# T06_preliminarySchematic_v3.net
KiCad netlist of a schematic drawn in EAGLE
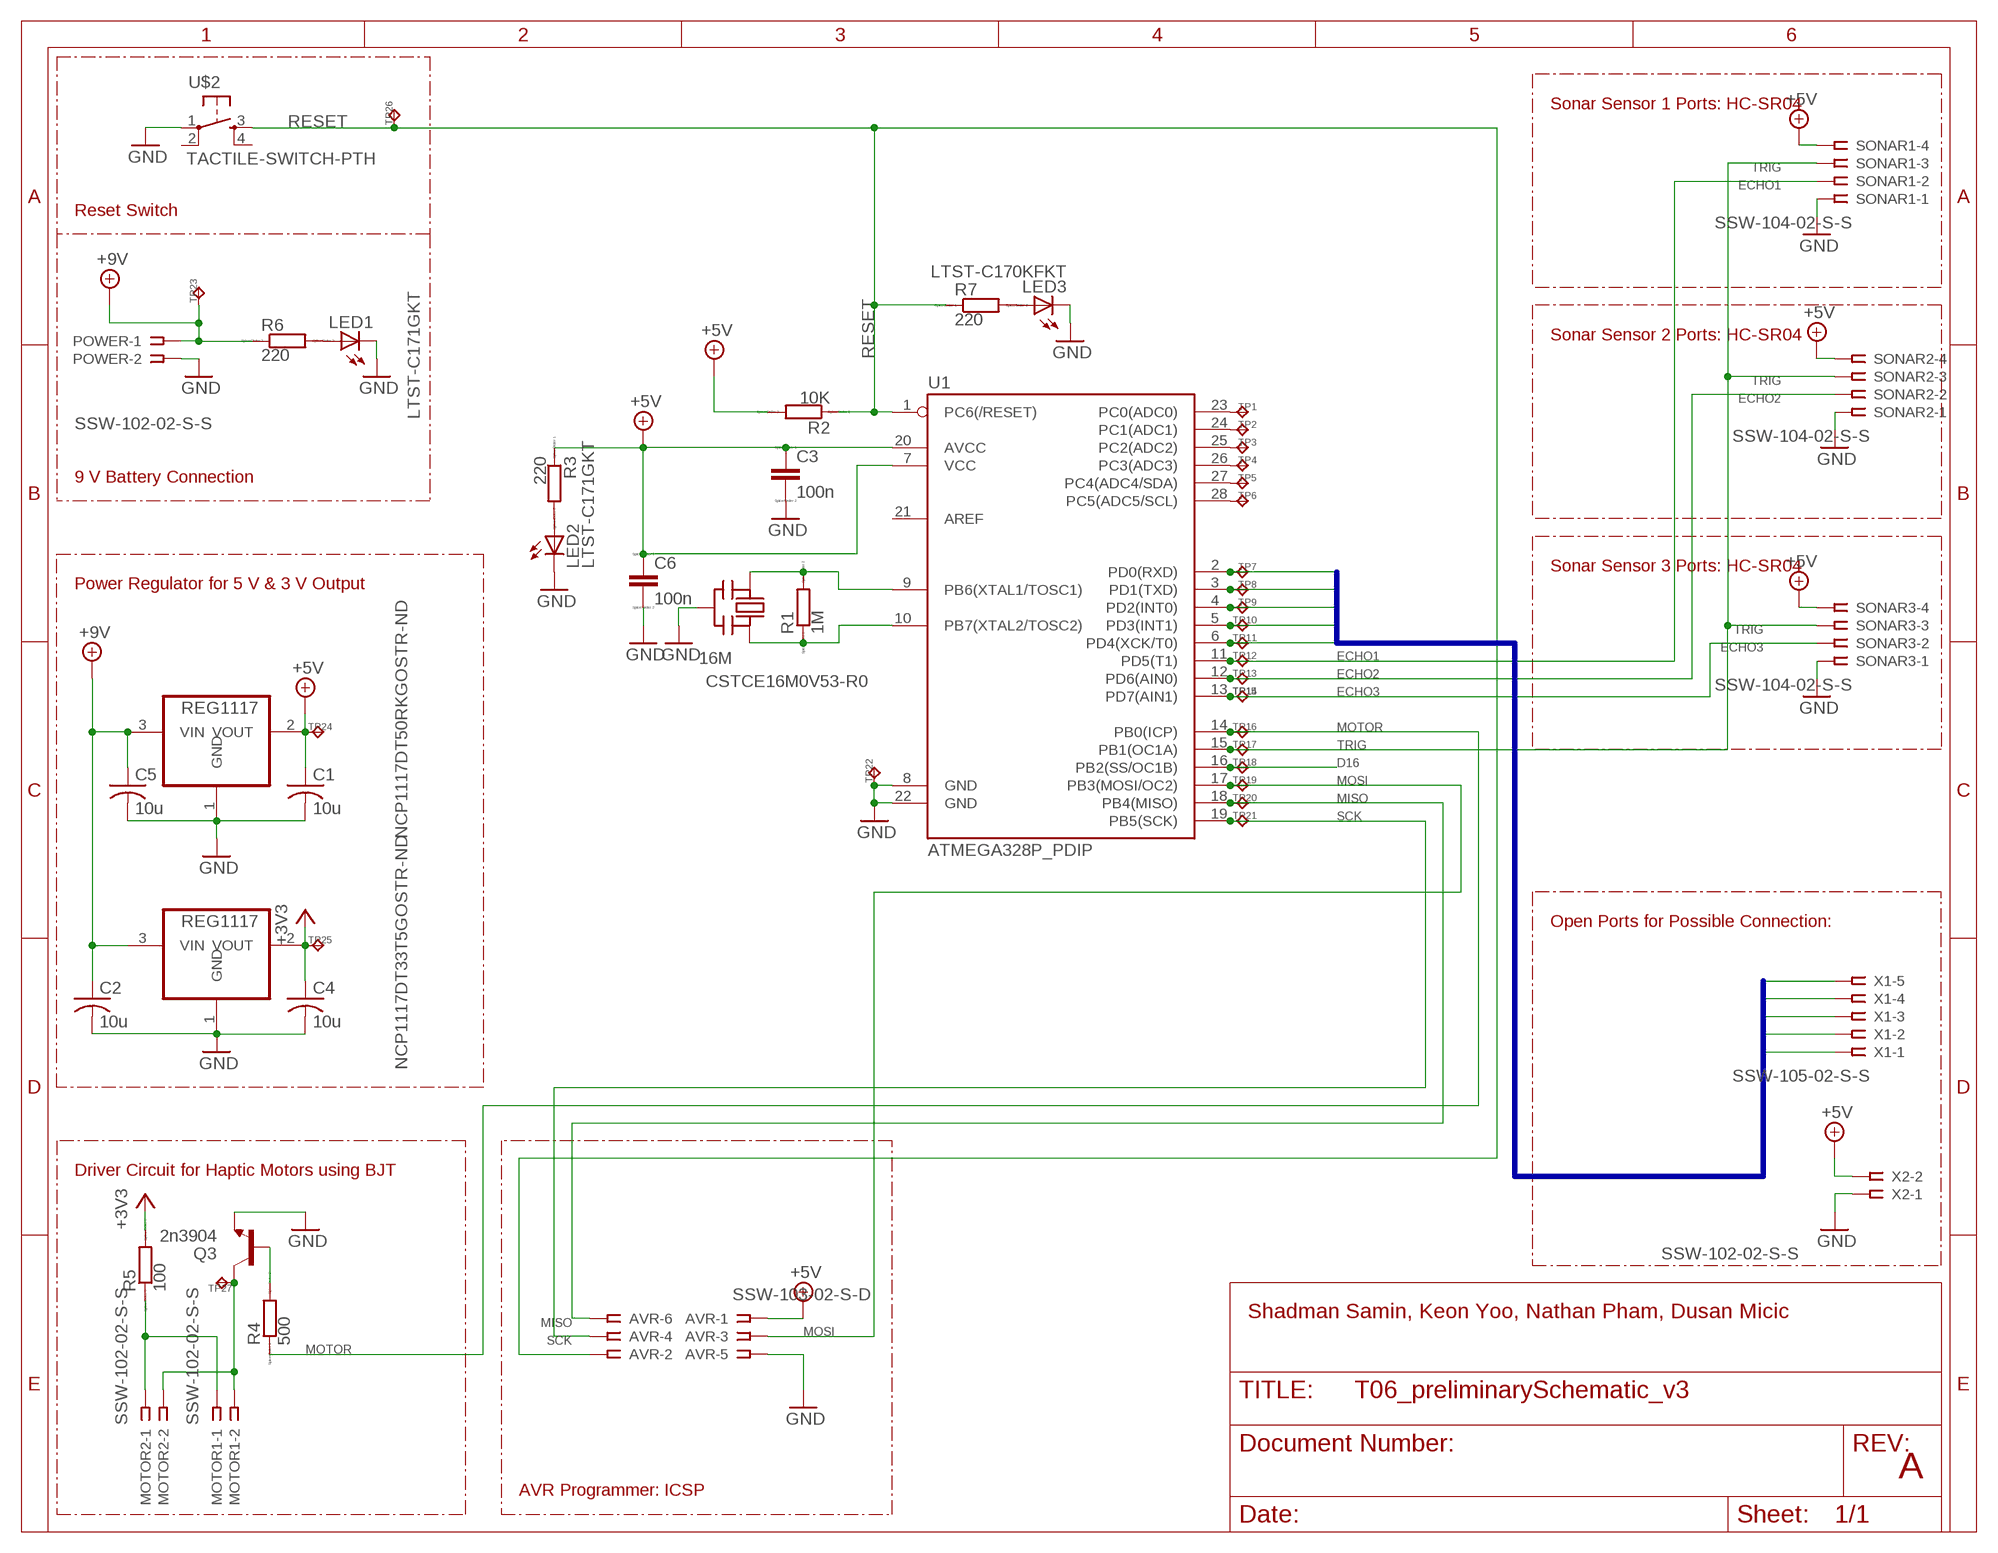
[diagram p0: schematic, sheet 1]

(export (version "E")
  (design (tool "Eeschema 10.0.6"))
  (components
    (comp (ref "AVR")
      (value "SSW-103-02-S-D")
      (footprint "eagle-import:SSW-103-02-S-D")
      (libsource (lib "eagle-import") (part "SSW-103-02-S-D"))
    )
    (comp (ref "C1")
      (value "10u")
      (footprint "eagle-import:C0805K")
      (libsource (lib "eagle-import") (part "C-USC0805K"))
    )
    (comp (ref "C2")
      (value "10u")
      (footprint "eagle-import:C0805K")
      (libsource (lib "eagle-import") (part "C-USC0805K"))
    )
    (comp (ref "C3")
      (value "100n")
      (footprint "eagle-import:C1005")
      (libsource (lib "eagle-import") (part "CC1005"))
    )
    (comp (ref "C4")
      (value "10u")
      (footprint "eagle-import:C0805K")
      (libsource (lib "eagle-import") (part "C-USC0805K"))
    )
    (comp (ref "C5")
      (value "10u")
      (footprint "eagle-import:C0805K")
      (libsource (lib "eagle-import") (part "C-USC0805K"))
    )
    (comp (ref "C6")
      (value "100n")
      (footprint "eagle-import:C1005")
      (libsource (lib "eagle-import") (part "CC1005"))
    )
    (comp (ref "CSTCE16M0V53-R0")
      (value "16M")
      (footprint "eagle-import:CSTCR-G")
      (libsource (lib "eagle-import") (part "CERMOSCILL-CSTCRG"))
    )
    (comp (ref "LED1")
      (value "LTST-C171GKT")
      (footprint "eagle-import:CHIPLED_0805")
      (libsource (lib "eagle-import") (part "LEDCHIPLED_0805"))
    )
    (comp (ref "LED2")
      (value "LTST-C171GKT")
      (footprint "eagle-import:CHIP-LED0805")
      (libsource (lib "eagle-import") (part "LEDCHIP-LED0805"))
    )
    (comp (ref "LED3")
      (value "LTST-C170KFKT")
      (footprint "eagle-import:CHIP-LED0805")
      (libsource (lib "eagle-import") (part "LEDCHIP-LED0805"))
    )
    (comp (ref "MOTOR1")
      (value "SSW-102-02-S-S")
      (footprint "eagle-import:SSW-102-02-S-S")
      (libsource (lib "eagle-import") (part "SSW-102-02-S-S"))
    )
    (comp (ref "MOTOR2")
      (value "SSW-102-02-S-S")
      (footprint "eagle-import:SSW-102-02-S-S")
      (libsource (lib "eagle-import") (part "SSW-102-02-S-S"))
    )
    (comp (ref "NCP1117DT33T5GOSTR-ND")
      (value "REG1117")
      (footprint "eagle-import:SOT223")
      (libsource (lib "eagle-import") (part "REG1117"))
    )
    (comp (ref "NCP1117DT50RKGOSTR-ND")
      (value "REG1117")
      (footprint "eagle-import:SOT223")
      (libsource (lib "eagle-import") (part "REG1117"))
    )
    (comp (ref "POWER")
      (value "SSW-102-02-S-S")
      (footprint "eagle-import:SSW-102-02-S-S")
      (libsource (lib "eagle-import") (part "SSW-102-02-S-S"))
    )
    (comp (ref "Q3")
      (value "2n3904")
      (footprint "eagle-import:TO-92")
      (libsource (lib "eagle-import") (part "TRANSISTOR_NPN2N3904"))
    )
    (comp (ref "R1")
      (value "1M")
      (footprint "eagle-import:R0603")
      (libsource (lib "eagle-import") (part "RR0603"))
    )
    (comp (ref "R2")
      (value "10K")
      (footprint "eagle-import:R0603")
      (libsource (lib "eagle-import") (part "RR0603"))
    )
    (comp (ref "R3")
      (value "220")
      (footprint "eagle-import:R0603")
      (libsource (lib "eagle-import") (part "RR0603"))
    )
    (comp (ref "R4")
      (value "500")
      (footprint "eagle-import:R0603")
      (libsource (lib "eagle-import") (part "RR0603"))
    )
    (comp (ref "R5")
      (value "100")
      (footprint "eagle-import:R0603")
      (libsource (lib "eagle-import") (part "RR0603"))
    )
    (comp (ref "R6")
      (value "220")
      (footprint "eagle-import:R0603")
      (libsource (lib "eagle-import") (part "RR0603"))
    )
    (comp (ref "R7")
      (value "220")
      (footprint "eagle-import:R0603")
      (libsource (lib "eagle-import") (part "RR0603"))
    )
    (comp (ref "SONAR1")
      (value "SSW-104-02-S-S")
      (footprint "eagle-import:SSW-104-02-S-S")
      (libsource (lib "eagle-import") (part "SSW-104-02-S-S"))
    )
    (comp (ref "SONAR2")
      (value "SSW-104-02-S-S")
      (footprint "eagle-import:SSW-104-02-S-S")
      (libsource (lib "eagle-import") (part "SSW-104-02-S-S"))
    )
    (comp (ref "SONAR3")
      (value "SSW-104-02-S-S")
      (footprint "eagle-import:SSW-104-02-S-S")
      (libsource (lib "eagle-import") (part "SSW-104-02-S-S"))
    )
    (comp (ref "TP1")
      (value "TPPAD1-13")
      (footprint "eagle-import:P1-13")
      (libsource (lib "eagle-import") (part "TPPAD1-13"))
    )
    (comp (ref "TP2")
      (value "TPPAD1-13")
      (footprint "eagle-import:P1-13")
      (libsource (lib "eagle-import") (part "TPPAD1-13"))
    )
    (comp (ref "TP3")
      (value "TPPAD1-13")
      (footprint "eagle-import:P1-13")
      (libsource (lib "eagle-import") (part "TPPAD1-13"))
    )
    (comp (ref "TP4")
      (value "TPPAD1-13")
      (footprint "eagle-import:P1-13")
      (libsource (lib "eagle-import") (part "TPPAD1-13"))
    )
    (comp (ref "TP5")
      (value "TPPAD1-13")
      (footprint "eagle-import:P1-13")
      (libsource (lib "eagle-import") (part "TPPAD1-13"))
    )
    (comp (ref "TP6")
      (value "TPPAD1-13")
      (footprint "eagle-import:P1-13")
      (libsource (lib "eagle-import") (part "TPPAD1-13"))
    )
    (comp (ref "TP7")
      (value "TPPAD1-13")
      (footprint "eagle-import:P1-13")
      (libsource (lib "eagle-import") (part "TPPAD1-13"))
    )
    (comp (ref "TP8")
      (value "TPPAD1-13")
      (footprint "eagle-import:P1-13")
      (libsource (lib "eagle-import") (part "TPPAD1-13"))
    )
    (comp (ref "TP9")
      (value "TPPAD1-13")
      (footprint "eagle-import:P1-13")
      (libsource (lib "eagle-import") (part "TPPAD1-13"))
    )
    (comp (ref "TP10")
      (value "TPPAD1-13")
      (footprint "eagle-import:P1-13")
      (libsource (lib "eagle-import") (part "TPPAD1-13"))
    )
    (comp (ref "TP11")
      (value "TPPAD1-13")
      (footprint "eagle-import:P1-13")
      (libsource (lib "eagle-import") (part "TPPAD1-13"))
    )
    (comp (ref "TP12")
      (value "TPPAD1-13")
      (footprint "eagle-import:P1-13")
      (libsource (lib "eagle-import") (part "TPPAD1-13"))
    )
    (comp (ref "TP13")
      (value "TPPAD1-13")
      (footprint "eagle-import:P1-13")
      (libsource (lib "eagle-import") (part "TPPAD1-13"))
    )
    (comp (ref "TP14")
      (value "TPPAD1-13")
      (footprint "eagle-import:P1-13")
      (libsource (lib "eagle-import") (part "TPPAD1-13"))
    )
    (comp (ref "TP15")
      (value "TPPAD1-13")
      (footprint "eagle-import:P1-13")
      (libsource (lib "eagle-import") (part "TPPAD1-13"))
    )
    (comp (ref "TP16")
      (value "TPPAD1-13")
      (footprint "eagle-import:P1-13")
      (libsource (lib "eagle-import") (part "TPPAD1-13"))
    )
    (comp (ref "TP17")
      (value "TPPAD1-13")
      (footprint "eagle-import:P1-13")
      (libsource (lib "eagle-import") (part "TPPAD1-13"))
    )
    (comp (ref "TP18")
      (value "TPPAD1-13")
      (footprint "eagle-import:P1-13")
      (libsource (lib "eagle-import") (part "TPPAD1-13"))
    )
    (comp (ref "TP19")
      (value "TPPAD1-13")
      (footprint "eagle-import:P1-13")
      (libsource (lib "eagle-import") (part "TPPAD1-13"))
    )
    (comp (ref "TP20")
      (value "TPPAD1-13")
      (footprint "eagle-import:P1-13")
      (libsource (lib "eagle-import") (part "TPPAD1-13"))
    )
    (comp (ref "TP21")
      (value "TPPAD1-13")
      (footprint "eagle-import:P1-13")
      (libsource (lib "eagle-import") (part "TPPAD1-13"))
    )
    (comp (ref "TP22")
      (value "TPPAD1-13")
      (footprint "eagle-import:P1-13")
      (libsource (lib "eagle-import") (part "TPPAD1-13"))
    )
    (comp (ref "TP23")
      (value "TPPAD1-13")
      (footprint "eagle-import:P1-13")
      (libsource (lib "eagle-import") (part "TPPAD1-13"))
    )
    (comp (ref "TP24")
      (value "TPPAD1-13")
      (footprint "eagle-import:P1-13")
      (libsource (lib "eagle-import") (part "TPPAD1-13"))
    )
    (comp (ref "TP25")
      (value "TPPAD1-13")
      (footprint "eagle-import:P1-13")
      (libsource (lib "eagle-import") (part "TPPAD1-13"))
    )
    (comp (ref "TP26")
      (value "TPPAD1-13")
      (footprint "eagle-import:P1-13")
      (libsource (lib "eagle-import") (part "TPPAD1-13"))
    )
    (comp (ref "TP27")
      (value "TPPAD1-13")
      (footprint "eagle-import:P1-13")
      (libsource (lib "eagle-import") (part "TPPAD1-13"))
    )
    (comp (ref "U$2")
      (value "TACTILE-SWITCH-PTH")
      (footprint "eagle-import:TAC-SWITCH-PTH")
      (libsource (lib "eagle-import") (part "TACTILE-SWITCH-PTH"))
    )
    (comp (ref "U1")
      (value "ATMEGA328P_PDIP")
      (footprint "eagle-import:DIL28-3")
      (libsource (lib "eagle-import") (part "ATMEGA328P_PDIP"))
    )
    (comp (ref "X1")
      (value "SSW-105-02-S-S")
      (footprint "eagle-import:SSW-105-02-S-S")
      (libsource (lib "eagle-import") (part "SSW-105-02-S-S"))
    )
    (comp (ref "X2")
      (value "SSW-102-02-S-S")
      (footprint "eagle-import:SSW-102-02-S-S")
      (libsource (lib "eagle-import") (part "SSW-102-02-S-S"))
    )
  )
  (nets
    (net (code "1") (name "+3V3") (class "Default")
      (node (ref "C4") (pin "1") (pinfunction "1_1") (pintype "passive"))
      (node (ref "NCP1117DT33T5GOSTR-ND") (pin "2") (pinfunction "VOUT_2") (pintype "output"))
      (node (ref "R5") (pin "2") (pinfunction "2_2") (pintype "passive"))
      (node (ref "TP25") (pin "TP") (pinfunction "TP_TP") (pintype "input"))
    )
    (net (code "2") (name "+5V") (class "Default")
      (node (ref "AVR") (pin "1") (pinfunction "1_1") (pintype "passive"))
      (node (ref "C1") (pin "1") (pinfunction "1_1") (pintype "passive"))
      (node (ref "C3") (pin "1") (pinfunction "1_1") (pintype "passive"))
      (node (ref "C6") (pin "1") (pinfunction "1_1") (pintype "passive"))
      (node (ref "NCP1117DT50RKGOSTR-ND") (pin "2") (pinfunction "VOUT_2") (pintype "output"))
      (node (ref "R2") (pin "2") (pinfunction "2_2") (pintype "passive"))
      (node (ref "R3") (pin "1") (pinfunction "1_1") (pintype "passive"))
      (node (ref "SONAR1") (pin "4") (pinfunction "1_4") (pintype "passive"))
      (node (ref "SONAR2") (pin "4") (pinfunction "1_4") (pintype "passive"))
      (node (ref "SONAR3") (pin "4") (pinfunction "1_4") (pintype "passive"))
      (node (ref "TP24") (pin "TP") (pinfunction "TP_TP") (pintype "input"))
      (node (ref "U1") (pin "20") (pinfunction "AVCC_20") (pintype "bidirectional"))
      (node (ref "U1") (pin "7") (pinfunction "VCC_7") (pintype "bidirectional"))
      (node (ref "X2") (pin "2") (pinfunction "1_2") (pintype "passive"))
    )
    (net (code "3") (name "+9V") (class "Default")
      (node (ref "C2") (pin "1") (pinfunction "1_1") (pintype "passive"))
      (node (ref "C5") (pin "1") (pinfunction "1_1") (pintype "passive"))
      (node (ref "NCP1117DT33T5GOSTR-ND") (pin "3") (pinfunction "VIN_3") (pintype "input"))
      (node (ref "NCP1117DT50RKGOSTR-ND") (pin "3") (pinfunction "VIN_3") (pintype "input"))
      (node (ref "POWER") (pin "1") (pinfunction "1_1") (pintype "passive"))
      (node (ref "R6") (pin "1") (pinfunction "1_1") (pintype "passive"))
      (node (ref "TP23") (pin "TP") (pinfunction "TP_TP") (pintype "input"))
    )
    (net (code "4") (name "/BU0") (class "Default")
      (node (ref "TP7") (pin "TP") (pinfunction "TP_TP") (pintype "input"))
      (node (ref "U1") (pin "2") (pinfunction "PD0(RXD)_2") (pintype "bidirectional"))
      (node (ref "X1") (pin "1") (pinfunction "1_1") (pintype "passive"))
    )
    (net (code "5") (name "/BU1") (class "Default")
      (node (ref "TP8") (pin "TP") (pinfunction "TP_TP") (pintype "input"))
      (node (ref "U1") (pin "3") (pinfunction "PD1(TXD)_3") (pintype "bidirectional"))
      (node (ref "X1") (pin "2") (pinfunction "1_2") (pintype "passive"))
    )
    (net (code "6") (name "/BU2") (class "Default")
      (node (ref "TP9") (pin "TP") (pinfunction "TP_TP") (pintype "input"))
      (node (ref "U1") (pin "4") (pinfunction "PD2(INT0)_4") (pintype "bidirectional"))
      (node (ref "X1") (pin "3") (pinfunction "1_3") (pintype "passive"))
    )
    (net (code "7") (name "/BU3") (class "Default")
      (node (ref "TP10") (pin "TP") (pinfunction "TP_TP") (pintype "input"))
      (node (ref "U1") (pin "5") (pinfunction "PD3(INT1)_5") (pintype "bidirectional"))
      (node (ref "X1") (pin "4") (pinfunction "1_4") (pintype "passive"))
    )
    (net (code "8") (name "/BU4") (class "Default")
      (node (ref "TP11") (pin "TP") (pinfunction "TP_TP") (pintype "input"))
      (node (ref "U1") (pin "6") (pinfunction "PD4(XCK/T0)_6") (pintype "bidirectional"))
      (node (ref "X1") (pin "5") (pinfunction "1_5") (pintype "passive"))
    )
    (net (code "9") (name "/D16") (class "Default")
      (node (ref "TP18") (pin "TP") (pinfunction "TP_TP") (pintype "input"))
      (node (ref "U1") (pin "16") (pinfunction "PB2(SS/OC1B)_16") (pintype "bidirectional"))
    )
    (net (code "10") (name "/ECHO1") (class "Default")
      (node (ref "SONAR1") (pin "2") (pinfunction "1_2") (pintype "passive"))
      (node (ref "TP12") (pin "TP") (pinfunction "TP_TP") (pintype "input"))
      (node (ref "U1") (pin "11") (pinfunction "PD5(T1)_11") (pintype "bidirectional"))
    )
    (net (code "11") (name "/ECHO2") (class "Default")
      (node (ref "SONAR2") (pin "2") (pinfunction "1_2") (pintype "passive"))
      (node (ref "TP13") (pin "TP") (pinfunction "TP_TP") (pintype "input"))
      (node (ref "U1") (pin "12") (pinfunction "PD6(AIN0)_12") (pintype "bidirectional"))
    )
    (net (code "12") (name "/ECHO3") (class "Default")
      (node (ref "SONAR3") (pin "2") (pinfunction "1_2") (pintype "passive"))
      (node (ref "TP14") (pin "TP") (pinfunction "TP_TP") (pintype "input"))
      (node (ref "TP15") (pin "TP") (pinfunction "TP_TP") (pintype "input"))
      (node (ref "U1") (pin "13") (pinfunction "PD7(AIN1)_13") (pintype "bidirectional"))
    )
    (net (code "13") (name "/MISO") (class "Default")
      (node (ref "AVR") (pin "6") (pinfunction "1_6") (pintype "passive"))
      (node (ref "TP20") (pin "TP") (pinfunction "TP_TP") (pintype "input"))
      (node (ref "U1") (pin "18") (pinfunction "PB4(MISO)_18") (pintype "bidirectional"))
    )
    (net (code "14") (name "/MOSI") (class "Default")
      (node (ref "AVR") (pin "3") (pinfunction "1_3") (pintype "passive"))
      (node (ref "TP19") (pin "TP") (pinfunction "TP_TP") (pintype "input"))
      (node (ref "U1") (pin "17") (pinfunction "PB3(MOSI/OC2)_17") (pintype "bidirectional"))
    )
    (net (code "15") (name "/MOTOR") (class "Default")
      (node (ref "R4") (pin "1") (pinfunction "1_1") (pintype "passive"))
      (node (ref "TP16") (pin "TP") (pinfunction "TP_TP") (pintype "input"))
      (node (ref "U1") (pin "14") (pinfunction "PB0(ICP)_14") (pintype "bidirectional"))
    )
    (net (code "16") (name "/RESET") (class "Default")
      (node (ref "AVR") (pin "2") (pinfunction "1_2") (pintype "passive"))
      (node (ref "R2") (pin "1") (pinfunction "1_1") (pintype "passive"))
      (node (ref "R7") (pin "1") (pinfunction "1_1") (pintype "passive"))
      (node (ref "TP26") (pin "TP") (pinfunction "TP_TP") (pintype "input"))
      (node (ref "U$2") (pin "3") (pinfunction "3_3") (pintype "passive"))
      (node (ref "U1") (pin "1") (pinfunction "PC6(/RESET)_1") (pintype "bidirectional"))
    )
    (net (code "17") (name "/SCK") (class "Default")
      (node (ref "AVR") (pin "4") (pinfunction "1_4") (pintype "passive"))
      (node (ref "TP21") (pin "TP") (pinfunction "TP_TP") (pintype "input"))
      (node (ref "U1") (pin "19") (pinfunction "PB5(SCK)_19") (pintype "bidirectional"))
    )
    (net (code "18") (name "/TRIG") (class "Default")
      (node (ref "SONAR1") (pin "3") (pinfunction "1_3") (pintype "passive"))
      (node (ref "SONAR2") (pin "3") (pinfunction "1_3") (pintype "passive"))
      (node (ref "SONAR3") (pin "3") (pinfunction "1_3") (pintype "passive"))
      (node (ref "TP17") (pin "TP") (pinfunction "TP_TP") (pintype "input"))
      (node (ref "U1") (pin "15") (pinfunction "PB1(OC1A)_15") (pintype "bidirectional"))
    )
    (net (code "19") (name "GND") (class "Default")
      (node (ref "AVR") (pin "5") (pinfunction "1_5") (pintype "passive"))
      (node (ref "C1") (pin "2") (pinfunction "2_2") (pintype "passive"))
      (node (ref "C2") (pin "2") (pinfunction "2_2") (pintype "passive"))
      (node (ref "C3") (pin "2") (pinfunction "2_2") (pintype "passive"))
      (node (ref "C4") (pin "2") (pinfunction "2_2") (pintype "passive"))
      (node (ref "C5") (pin "2") (pinfunction "2_2") (pintype "passive"))
      (node (ref "C6") (pin "2") (pinfunction "2_2") (pintype "passive"))
      (node (ref "CSTCE16M0V53-R0") (pin "2") (pinfunction "GND_2") (pintype "bidirectional"))
      (node (ref "LED1") (pin "C") (pinfunction "C_C") (pintype "passive"))
      (node (ref "LED2") (pin "C") (pinfunction "C_C") (pintype "passive"))
      (node (ref "LED3") (pin "C") (pinfunction "C_C") (pintype "passive"))
      (node (ref "NCP1117DT33T5GOSTR-ND") (pin "1") (pinfunction "GND_1") (pintype "power_in"))
      (node (ref "NCP1117DT50RKGOSTR-ND") (pin "1") (pinfunction "GND_1") (pintype "power_in"))
      (node (ref "POWER") (pin "2") (pinfunction "1_2") (pintype "passive"))
      (node (ref "Q3") (pin "1") (pinfunction "E_1") (pintype "passive"))
      (node (ref "SONAR1") (pin "1") (pinfunction "1_1") (pintype "passive"))
      (node (ref "SONAR2") (pin "1") (pinfunction "1_1") (pintype "passive"))
      (node (ref "SONAR3") (pin "1") (pinfunction "1_1") (pintype "passive"))
      (node (ref "TP22") (pin "TP") (pinfunction "TP_TP") (pintype "input"))
      (node (ref "U$2") (pin "1") (pinfunction "1_1") (pintype "passive"))
      (node (ref "U1") (pin "22") (pinfunction "GND_22") (pintype "bidirectional"))
      (node (ref "U1") (pin "8") (pinfunction "GND_8") (pintype "bidirectional"))
      (node (ref "X2") (pin "1") (pinfunction "1_1") (pintype "passive"))
    )
    (net (code "20") (name "Net-(CSTCE16M0V53-R0-IN)") (class "Default")
      (node (ref "CSTCE16M0V53-R0") (pin "1") (pinfunction "IN_1") (pintype "bidirectional"))
      (node (ref "R1") (pin "2") (pinfunction "2_2") (pintype "passive"))
      (node (ref "U1") (pin "9") (pinfunction "PB6(XTAL1/TOSC1)_9") (pintype "bidirectional"))
    )
    (net (code "21") (name "Net-(CSTCE16M0V53-R0-OUT)") (class "Default")
      (node (ref "CSTCE16M0V53-R0") (pin "3") (pinfunction "OUT_3") (pintype "bidirectional"))
      (node (ref "R1") (pin "1") (pinfunction "1_1") (pintype "passive"))
      (node (ref "U1") (pin "10") (pinfunction "PB7(XTAL2/TOSC2)_10") (pintype "bidirectional"))
    )
    (net (code "22") (name "Net-(LED1-PadA)") (class "Default")
      (node (ref "LED1") (pin "A") (pinfunction "A_A") (pintype "passive"))
      (node (ref "R6") (pin "2") (pinfunction "2_2") (pintype "passive"))
    )
    (net (code "23") (name "Net-(LED2-PadA)") (class "Default")
      (node (ref "LED2") (pin "A") (pinfunction "A_A") (pintype "passive"))
      (node (ref "R3") (pin "2") (pinfunction "2_2") (pintype "passive"))
    )
    (net (code "24") (name "Net-(LED3-PadA)") (class "Default")
      (node (ref "LED3") (pin "A") (pinfunction "A_A") (pintype "passive"))
      (node (ref "R7") (pin "2") (pinfunction "2_2") (pintype "passive"))
    )
    (net (code "25") (name "Net-(MOTOR1-Pad1)") (class "Default")
      (node (ref "MOTOR1") (pin "1") (pinfunction "1_1") (pintype "passive"))
      (node (ref "MOTOR2") (pin "1") (pinfunction "1_1") (pintype "passive"))
      (node (ref "R5") (pin "1") (pinfunction "1_1") (pintype "passive"))
    )
    (net (code "26") (name "Net-(MOTOR1B-1)") (class "Default")
      (node (ref "MOTOR1") (pin "2") (pinfunction "1_2") (pintype "passive"))
      (node (ref "MOTOR2") (pin "2") (pinfunction "1_2") (pintype "passive"))
      (node (ref "Q3") (pin "3") (pinfunction "C_3") (pintype "passive"))
      (node (ref "TP27") (pin "TP") (pinfunction "TP_TP") (pintype "input"))
    )
    (net (code "27") (name "Net-(Q3-B)") (class "Default")
      (node (ref "Q3") (pin "2") (pinfunction "B_2") (pintype "passive"))
      (node (ref "R4") (pin "2") (pinfunction "2_2") (pintype "passive"))
    )
    (net (code "28") (name "Net-(U1-PC0(ADC0))") (class "Default")
      (node (ref "TP1") (pin "TP") (pinfunction "TP_TP") (pintype "input"))
      (node (ref "U1") (pin "23") (pinfunction "PC0(ADC0)_23") (pintype "bidirectional"))
    )
    (net (code "29") (name "Net-(U1-PC1(ADC1))") (class "Default")
      (node (ref "TP2") (pin "TP") (pinfunction "TP_TP") (pintype "input"))
      (node (ref "U1") (pin "24") (pinfunction "PC1(ADC1)_24") (pintype "bidirectional"))
    )
    (net (code "30") (name "Net-(U1-PC2(ADC2))") (class "Default")
      (node (ref "TP3") (pin "TP") (pinfunction "TP_TP") (pintype "input"))
      (node (ref "U1") (pin "25") (pinfunction "PC2(ADC2)_25") (pintype "bidirectional"))
    )
    (net (code "31") (name "Net-(U1-PC3(ADC3))") (class "Default")
      (node (ref "TP4") (pin "TP") (pinfunction "TP_TP") (pintype "input"))
      (node (ref "U1") (pin "26") (pinfunction "PC3(ADC3)_26") (pintype "bidirectional"))
    )
    (net (code "32") (name "Net-(U1-PC4(ADC4{slash}SDA))") (class "Default")
      (node (ref "TP5") (pin "TP") (pinfunction "TP_TP") (pintype "input"))
      (node (ref "U1") (pin "27") (pinfunction "PC4(ADC4/SDA)_27") (pintype "bidirectional"))
    )
    (net (code "33") (name "Net-(U1-PC5(ADC5{slash}SCL))") (class "Default")
      (node (ref "TP6") (pin "TP") (pinfunction "TP_TP") (pintype "input"))
      (node (ref "U1") (pin "28") (pinfunction "PC5(ADC5/SCL)_28") (pintype "bidirectional"))
    )
    (net (code "34") (name "unconnected-(U$2-Pad2)") (class "Default")
      (node (ref "U$2") (pin "2") (pinfunction "2_2") (pintype "passive"))
    )
    (net (code "35") (name "unconnected-(U$2-Pad4)") (class "Default")
      (node (ref "U$2") (pin "4") (pinfunction "4_4") (pintype "passive"))
    )
    (net (code "36") (name "unconnected-(U1-AREF-Pad21)") (class "Default")
      (node (ref "U1") (pin "21") (pinfunction "AREF_21") (pintype "bidirectional"))
    )
  )
)
